# RxPCB_V1-3.net
KiCad netlist of a schematic drawn in EAGLE
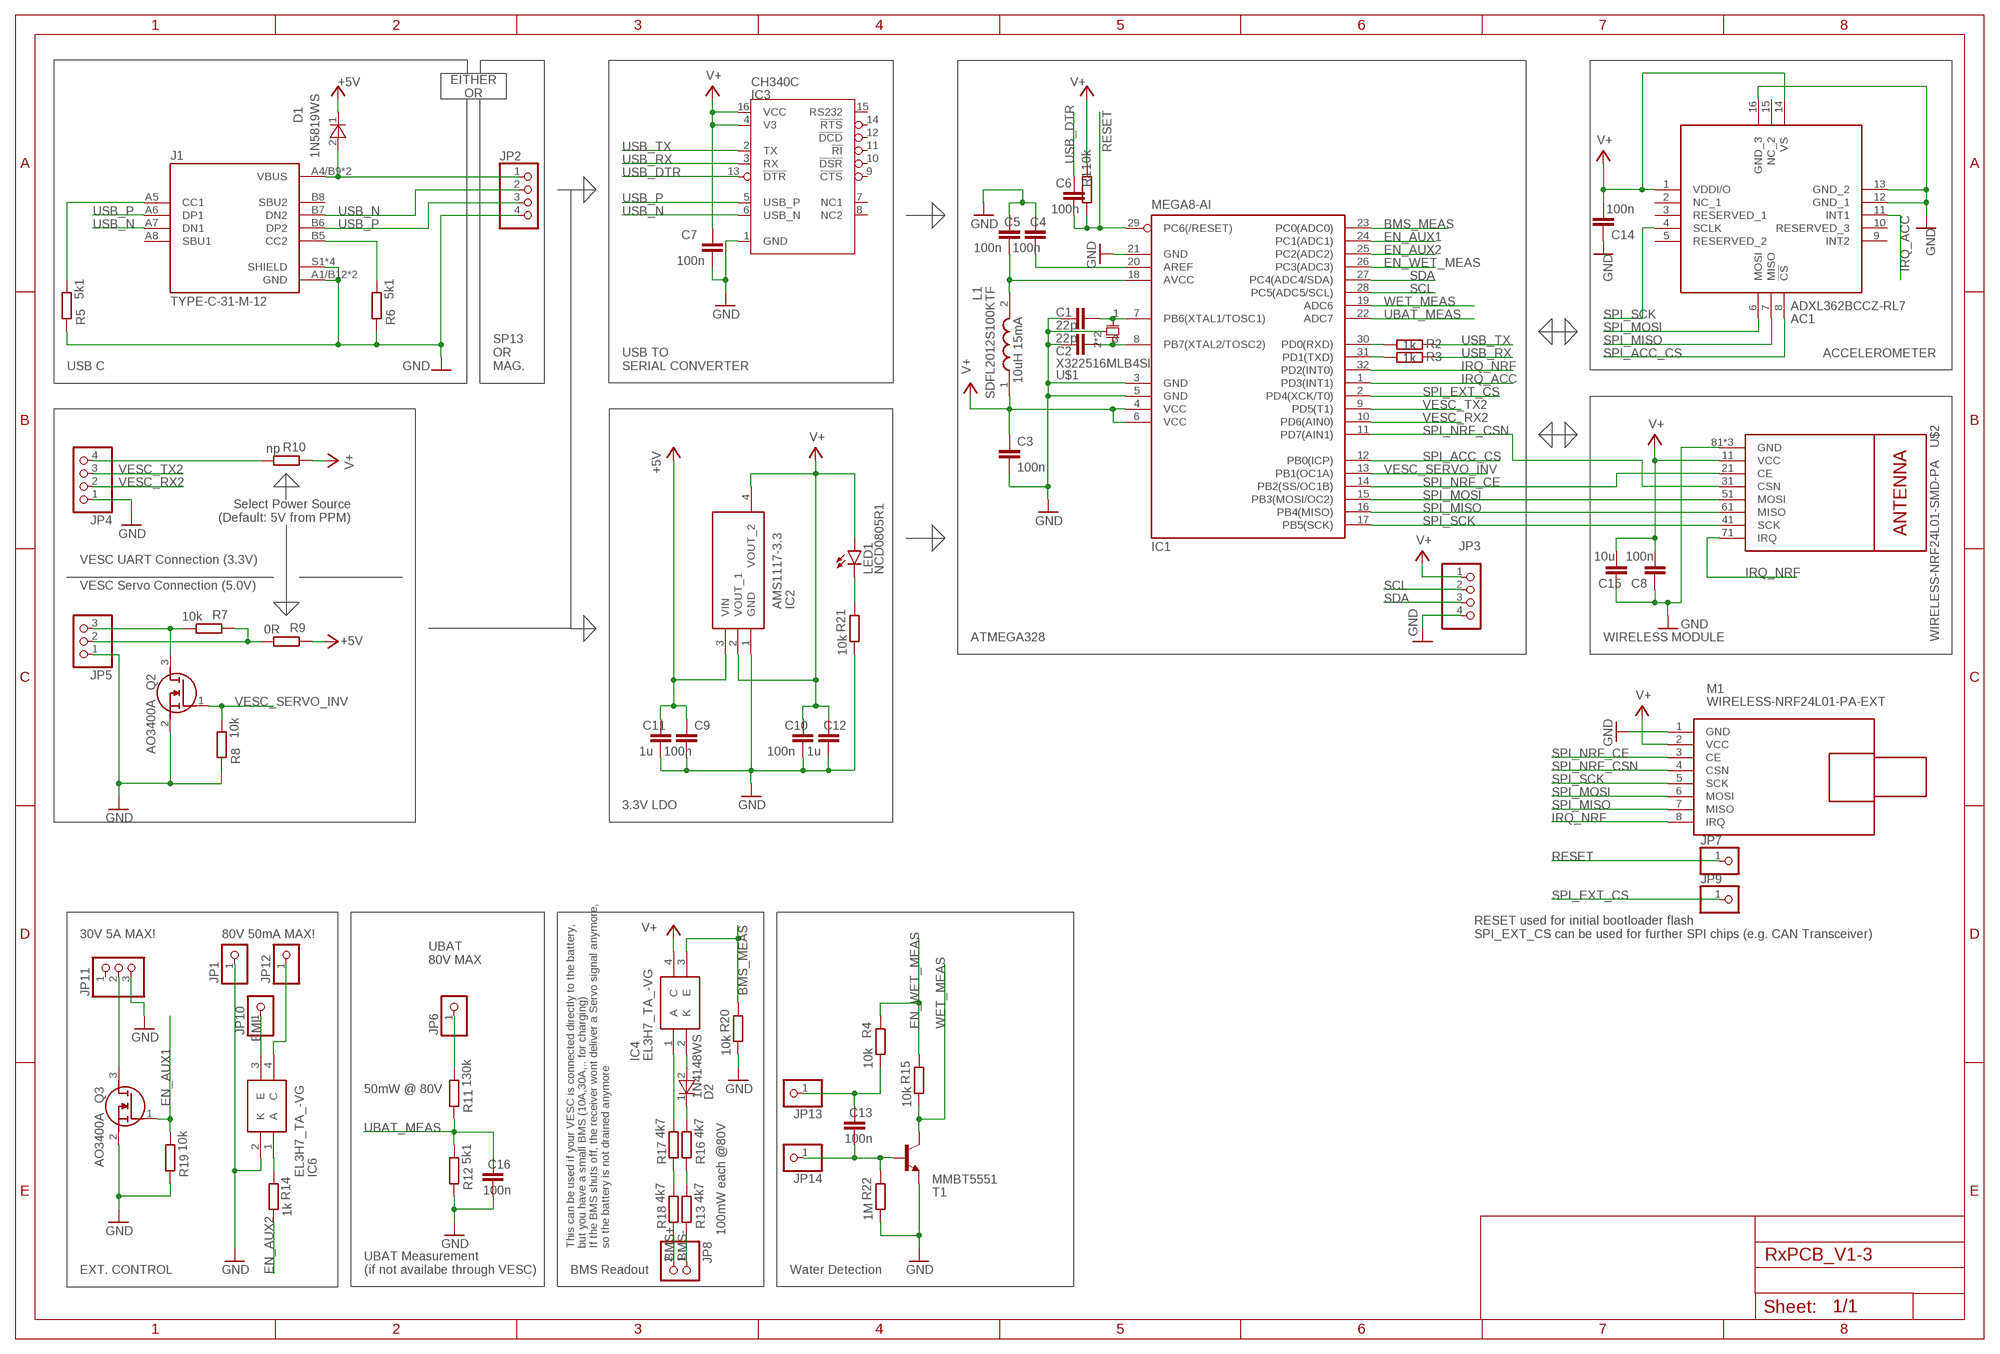
[diagram p0: schematic, sheet 1]

(export (version "E")
  (design (tool "Eeschema 10.0.6"))
  (components
    (comp (ref "AC1")
      (value "ADXL362BCCZ-RL7")
      (footprint "eagle-import:CC-16-4")
      (fields (field (name "MOUSER_PART_NUMBER") "584-ADXL362BCCZ-R7"))
      (libsource (lib "eagle-import") (part "ADXL362BCCZ-RL7"))
    )
    (comp (ref "C1")
      (value "22p")
      (footprint "eagle-import:C0603")
      (libsource (lib "eagle-import") (part "C-EUC0603"))
    )
    (comp (ref "C2")
      (value "22p")
      (footprint "eagle-import:C0603")
      (libsource (lib "eagle-import") (part "C-EUC0603"))
    )
    (comp (ref "C3")
      (value "100n")
      (footprint "eagle-import:C0603")
      (libsource (lib "eagle-import") (part "C-EUC0603"))
    )
    (comp (ref "C4")
      (value "100n")
      (footprint "eagle-import:C0603")
      (libsource (lib "eagle-import") (part "C-EUC0603"))
    )
    (comp (ref "C5")
      (value "100n")
      (footprint "eagle-import:C0603")
      (libsource (lib "eagle-import") (part "C-EUC0603"))
    )
    (comp (ref "C6")
      (value "100n")
      (footprint "eagle-import:C0603")
      (libsource (lib "eagle-import") (part "C-EUC0603"))
    )
    (comp (ref "C7")
      (value "100n")
      (footprint "eagle-import:C0603")
      (libsource (lib "eagle-import") (part "C-EUC0603"))
    )
    (comp (ref "C8")
      (value "100n")
      (footprint "eagle-import:C0603")
      (libsource (lib "eagle-import") (part "C-EUC0603"))
    )
    (comp (ref "C9")
      (value "100n")
      (footprint "eagle-import:C0603")
      (libsource (lib "eagle-import") (part "C-EUC0603"))
    )
    (comp (ref "C10")
      (value "100n")
      (footprint "eagle-import:C0603")
      (libsource (lib "eagle-import") (part "C-EUC0603"))
    )
    (comp (ref "C11")
      (value "1u")
      (footprint "eagle-import:C0603")
      (libsource (lib "eagle-import") (part "C-EUC0603"))
    )
    (comp (ref "C12")
      (value "1u")
      (footprint "eagle-import:C0603")
      (libsource (lib "eagle-import") (part "C-EUC0603"))
    )
    (comp (ref "C13")
      (value "100n")
      (footprint "eagle-import:C0603")
      (libsource (lib "eagle-import") (part "C-EUC0603"))
    )
    (comp (ref "C14")
      (value "100n")
      (footprint "eagle-import:C0603")
      (libsource (lib "eagle-import") (part "C-EUC0603"))
    )
    (comp (ref "C15")
      (value "10u")
      (footprint "eagle-import:C0603")
      (libsource (lib "eagle-import") (part "C-EUC0603"))
    )
    (comp (ref "C16")
      (value "100n")
      (footprint "eagle-import:C0603")
      (libsource (lib "eagle-import") (part "C-EUC0603"))
    )
    (comp (ref "D1")
      (value "1N5819WS")
      (footprint "eagle-import:SODFL2512X90N")
      (fields
        (field (name "ARROW_PART_NUMBER") "1N4148WS")
        (field (name "MOUSER_PART_NUMBER") "512-1N4148WS")
      )
      (libsource (lib "eagle-import") (part "1N4148WS"))
    )
    (comp (ref "D2")
      (value "1N4148WS")
      (footprint "eagle-import:SODFL2512X90N")
      (fields (field (name "MOUSER_PART_NUMBER") "512-1N4148WS"))
      (libsource (lib "eagle-import") (part "1N4148WS"))
    )
    (comp (ref "IC1")
      (value "MEGA8-AI")
      (footprint "eagle-import:TQFP32-08")
      (fields (field (name "MPN") "ATMEGA8-16AU"))
      (libsource (lib "eagle-import") (part "MEGA8-AI"))
    )
    (comp (ref "IC2")
      (value "AMS1117-3.3")
      (footprint "eagle-import:SOT229P700X180-4N")
      (libsource (lib "eagle-import") (part "AMS1117-3.3"))
    )
    (comp (ref "IC3")
      (value "CH340C")
      (footprint "eagle-import:SOIC16N")
      (libsource (lib "eagle-import") (part "CH340G"))
    )
    (comp (ref "IC4")
      (value "EL3H7_TA_-VG")
      (footprint "eagle-import:SOIC127P700X200-4N")
      (fields
        (field (name "ARROW_PART_NUMBER") "EL3H7(TA)-VG")
        (field (name "MOUSER_PART_NUMBER") "638-EL3H7TAVG")
      )
      (libsource (lib "eagle-import") (part "EL3H7_TA_-VG"))
    )
    (comp (ref "IC6")
      (value "EL3H7_TA_-VG")
      (footprint "eagle-import:SOIC127P700X200-4N")
      (fields
        (field (name "ARROW_PART_NUMBER") "EL3H7(TA)-VG")
        (field (name "MOUSER_PART_NUMBER") "638-EL3H7TAVG")
      )
      (libsource (lib "eagle-import") (part "EL3H7_TA_-VG"))
    )
    (comp (ref "J1")
      (value "TYPE-C-31-M-12")
      (footprint "eagle-import:HRO_TYPE-C-31-M-12")
      (fields (field (name "MF") "HRO Electronics Co., Ltd."))
      (libsource (lib "eagle-import") (part "TYPE-C-31-M-12"))
    )
    (comp (ref "JP1")
      (value "PINHD-1X1")
      (footprint "eagle-import:1X01")
      (libsource (lib "eagle-import") (part "PINHD-1X1"))
    )
    (comp (ref "JP2")
      (value "PINHD-1X4")
      (footprint "eagle-import:1X04")
      (libsource (lib "eagle-import") (part "PINHD-1X4"))
    )
    (comp (ref "JP3")
      (value "PINHD-1X4")
      (footprint "eagle-import:1X04")
      (libsource (lib "eagle-import") (part "PINHD-1X4"))
    )
    (comp (ref "JP4")
      (value "PINHD-1X4")
      (footprint "eagle-import:1X04")
      (libsource (lib "eagle-import") (part "PINHD-1X4"))
    )
    (comp (ref "JP5")
      (value "PINHD-1X3")
      (footprint "eagle-import:1X03")
      (libsource (lib "eagle-import") (part "PINHD-1X3"))
    )
    (comp (ref "JP6")
      (value "PINHD-1X1")
      (footprint "eagle-import:1X01")
      (libsource (lib "eagle-import") (part "PINHD-1X1"))
    )
    (comp (ref "JP7")
      (value "PINHD-1X1")
      (footprint "eagle-import:1X01")
      (libsource (lib "eagle-import") (part "PINHD-1X1"))
    )
    (comp (ref "JP8")
      (value "PINHD-1X2")
      (footprint "eagle-import:1X02")
      (libsource (lib "eagle-import") (part "PINHD-1X2"))
    )
    (comp (ref "JP9")
      (value "PINHD-1X1")
      (footprint "eagle-import:1X01")
      (libsource (lib "eagle-import") (part "PINHD-1X1"))
    )
    (comp (ref "JP10")
      (value "PINHD-1X1")
      (footprint "eagle-import:1X01")
      (libsource (lib "eagle-import") (part "PINHD-1X1"))
    )
    (comp (ref "JP11")
      (value "PINHD-1X3")
      (footprint "eagle-import:1X03")
      (libsource (lib "eagle-import") (part "PINHD-1X3"))
    )
    (comp (ref "JP12")
      (value "PINHD-1X1")
      (footprint "eagle-import:1X01")
      (libsource (lib "eagle-import") (part "PINHD-1X1"))
    )
    (comp (ref "JP13")
      (value "PINHD-1X1")
      (footprint "eagle-import:1X01")
      (libsource (lib "eagle-import") (part "PINHD-1X1"))
    )
    (comp (ref "JP14")
      (value "PINHD-1X1")
      (footprint "eagle-import:1X01")
      (libsource (lib "eagle-import") (part "PINHD-1X1"))
    )
    (comp (ref "L1")
      (value "SDFL2012S100KTF")
      (footprint "eagle-import:INDC2112X105N")
      (fields (field (name "MANUFACTURER_PART_NUMBER") "SDFL2012Q2R7KTF"))
      (libsource (lib "eagle-import") (part "SDFL2012Q2R7KTF"))
    )
    (comp (ref "LED1")
      (value "NCD0805R1")
      (footprint "eagle-import:CHIP-LED0805")
      (libsource (lib "eagle-import") (part "LEDCHIP-LED0805"))
    )
    (comp (ref "M1")
      (value "WIRELESS-NRF24L01-PA-EXT")
      (footprint "eagle-import:WIRELESS-NRF24L01-PA-EXT")
      (libsource (lib "eagle-import") (part "WIRELESS-NRF24L01-PA-EXT"))
    )
    (comp (ref "Q2")
      (value "AO3400A")
      (footprint "eagle-import:SOT95P280X125-3N")
      (libsource (lib "eagle-import") (part "AO3400A"))
    )
    (comp (ref "Q3")
      (value "AO3400A")
      (footprint "eagle-import:SOT95P280X125-3N")
      (libsource (lib "eagle-import") (part "AO3400A"))
    )
    (comp (ref "R1")
      (value "10k")
      (footprint "eagle-import:R0603")
      (libsource (lib "eagle-import") (part "R-EU_R0603"))
    )
    (comp (ref "R2")
      (value "1k")
      (footprint "eagle-import:R0603")
      (libsource (lib "eagle-import") (part "R-EU_R0603"))
    )
    (comp (ref "R3")
      (value "1k")
      (footprint "eagle-import:R0603")
      (libsource (lib "eagle-import") (part "R-EU_R0603"))
    )
    (comp (ref "R4")
      (value "10k")
      (footprint "eagle-import:R0603")
      (libsource (lib "eagle-import") (part "R-EU_R0603"))
    )
    (comp (ref "R5")
      (value "5k1")
      (footprint "eagle-import:R0603")
      (libsource (lib "eagle-import") (part "R-EU_R0603"))
    )
    (comp (ref "R6")
      (value "5k1")
      (footprint "eagle-import:R0603")
      (libsource (lib "eagle-import") (part "R-EU_R0603"))
    )
    (comp (ref "R7")
      (value "10k")
      (footprint "eagle-import:R0603")
      (libsource (lib "eagle-import") (part "R-EU_R0603"))
    )
    (comp (ref "R8")
      (value "10k")
      (footprint "eagle-import:R0603")
      (libsource (lib "eagle-import") (part "R-EU_R0603"))
    )
    (comp (ref "R9")
      (value "0R")
      (footprint "eagle-import:R0603")
      (libsource (lib "eagle-import") (part "R-EU_R0603"))
    )
    (comp (ref "R10")
      (value "np")
      (footprint "eagle-import:R0603")
      (libsource (lib "eagle-import") (part "R-EU_R0603"))
    )
    (comp (ref "R11")
      (value "130k")
      (footprint "eagle-import:R0603")
      (libsource (lib "eagle-import") (part "R-EU_R0603"))
    )
    (comp (ref "R12")
      (value "5k1")
      (footprint "eagle-import:R0603")
      (libsource (lib "eagle-import") (part "R-EU_R0603"))
    )
    (comp (ref "R13")
      (value "4k7")
      (footprint "eagle-import:R0603")
      (libsource (lib "eagle-import") (part "R-EU_R0603"))
    )
    (comp (ref "R14")
      (value "1k")
      (footprint "eagle-import:R0603")
      (libsource (lib "eagle-import") (part "R-EU_R0603"))
    )
    (comp (ref "R15")
      (value "10k")
      (footprint "eagle-import:R0603")
      (libsource (lib "eagle-import") (part "R-EU_R0603"))
    )
    (comp (ref "R16")
      (value "4k7")
      (footprint "eagle-import:R0603")
      (libsource (lib "eagle-import") (part "R-EU_R0603"))
    )
    (comp (ref "R17")
      (value "4k7")
      (footprint "eagle-import:R0603")
      (libsource (lib "eagle-import") (part "R-EU_R0603"))
    )
    (comp (ref "R18")
      (value "4k7")
      (footprint "eagle-import:R0603")
      (libsource (lib "eagle-import") (part "R-EU_R0603"))
    )
    (comp (ref "R19")
      (value "10k")
      (footprint "eagle-import:R0603")
      (libsource (lib "eagle-import") (part "R-EU_R0603"))
    )
    (comp (ref "R20")
      (value "10k")
      (footprint "eagle-import:R0603")
      (libsource (lib "eagle-import") (part "R-EU_R0603"))
    )
    (comp (ref "R21")
      (value "10k")
      (footprint "eagle-import:R0603")
      (libsource (lib "eagle-import") (part "R-EU_R0603"))
    )
    (comp (ref "R22")
      (value "1M")
      (footprint "eagle-import:R0603")
      (libsource (lib "eagle-import") (part "R-EU_R0603"))
    )
    (comp (ref "T1")
      (value "MMBT5551")
      (footprint "eagle-import:SOT23-BEC")
      (libsource (lib "eagle-import") (part "-NPN-SOT23-BECBC847B"))
    )
    (comp (ref "U$1")
      (value "X322516MLB4SI")
      (footprint "eagle-import:X322516MLB4SI")
      (libsource (lib "eagle-import") (part "X322516_BETTER"))
    )
    (comp (ref "U$2")
      (value "WIRELESS-NRF24L01-SMD-PA")
      (footprint "eagle-import:WIRELESS-NRF24L01_SMD_PA")
      (libsource (lib "eagle-import") (part "WIRELESS-NRF24L01-SMD-PA"))
    )
  )
  (nets
    (net (code "1") (name "+5V") (class "Default")
      (node (ref "C11") (pin "1") (pinfunction "1_1") (pintype "passive"))
      (node (ref "C9") (pin "1") (pinfunction "1_1") (pintype "passive"))
      (node (ref "D1") (pin "1") (pinfunction "K_1") (pintype "bidirectional"))
      (node (ref "IC2") (pin "3") (pinfunction "VIN_3") (pintype "bidirectional"))
      (node (ref "R9") (pin "1") (pinfunction "1_1") (pintype "passive"))
    )
    (net (code "2") (name "/BMS+") (class "Default")
      (node (ref "JP8") (pin "2") (pinfunction "2_2") (pintype "passive"))
      (node (ref "R18") (pin "1") (pinfunction "1_1") (pintype "passive"))
    )
    (net (code "3") (name "/BMS-") (class "Default")
      (node (ref "JP8") (pin "1") (pinfunction "1_1") (pintype "passive"))
      (node (ref "R13") (pin "1") (pinfunction "1_1") (pintype "passive"))
    )
    (net (code "4") (name "/BMS_MEAS") (class "Default")
      (node (ref "IC1") (pin "23") (pinfunction "PC0(ADC0)_23") (pintype "bidirectional"))
      (node (ref "IC4") (pin "3") (pinfunction "E_3") (pintype "bidirectional"))
      (node (ref "R20") (pin "1") (pinfunction "1_1") (pintype "passive"))
    )
    (net (code "5") (name "/EMI") (class "Default")
      (node (ref "IC6") (pin "3") (pinfunction "E_3") (pintype "bidirectional"))
      (node (ref "JP10") (pin "1") (pinfunction "1_1") (pintype "passive"))
    )
    (net (code "6") (name "/EN_AUX1") (class "Default")
      (node (ref "IC1") (pin "24") (pinfunction "PC1(ADC1)_24") (pintype "bidirectional"))
      (node (ref "Q3") (pin "1") (pinfunction "G_1") (pintype "bidirectional"))
      (node (ref "R19") (pin "2") (pinfunction "2_2") (pintype "passive"))
    )
    (net (code "7") (name "/EN_AUX2") (class "Default")
      (node (ref "IC1") (pin "25") (pinfunction "PC2(ADC2)_25") (pintype "bidirectional"))
      (node (ref "R14") (pin "2") (pinfunction "2_2") (pintype "passive"))
    )
    (net (code "8") (name "/EN_WET_MEAS") (class "Default")
      (node (ref "IC1") (pin "26") (pinfunction "PC3(ADC3)_26") (pintype "bidirectional"))
      (node (ref "R15") (pin "1") (pinfunction "1_1") (pintype "passive"))
      (node (ref "R4") (pin "1") (pinfunction "1_1") (pintype "passive"))
    )
    (net (code "9") (name "/IRQ_ACC") (class "Default")
      (node (ref "AC1") (pin "11") (pinfunction "INT1_11") (pintype "input"))
      (node (ref "IC1") (pin "1") (pinfunction "PD3(INT1)_1") (pintype "bidirectional"))
    )
    (net (code "10") (name "/IRQ_NRF") (class "Default")
      (node (ref "IC1") (pin "32") (pinfunction "PD2(INT0)_32") (pintype "bidirectional"))
      (node (ref "M1") (pin "8") (pinfunction "IRQ_8") (pintype "bidirectional"))
      (node (ref "U$2") (pin "71") (pinfunction "IRQ_71") (pintype "bidirectional"))
    )
    (net (code "11") (name "/RESET") (class "Default")
      (node (ref "C6") (pin "2") (pinfunction "2_2") (pintype "passive"))
      (node (ref "IC1") (pin "29") (pinfunction "PC6(/RESET)_29") (pintype "bidirectional"))
      (node (ref "JP7") (pin "1") (pinfunction "1_1") (pintype "passive"))
      (node (ref "R1") (pin "1") (pinfunction "1_1") (pintype "passive"))
    )
    (net (code "12") (name "/SCL") (class "Default")
      (node (ref "IC1") (pin "28") (pinfunction "PC5(ADC5/SCL)_28") (pintype "bidirectional"))
      (node (ref "JP3") (pin "2") (pinfunction "2_2") (pintype "passive"))
    )
    (net (code "13") (name "/SDA") (class "Default")
      (node (ref "IC1") (pin "27") (pinfunction "PC4(ADC4/SDA)_27") (pintype "bidirectional"))
      (node (ref "JP3") (pin "3") (pinfunction "3_3") (pintype "passive"))
    )
    (net (code "14") (name "/SPI_ACC_CS") (class "Default")
      (node (ref "AC1") (pin "8") (pinfunction "~{CS}_8") (pintype "input"))
      (node (ref "IC1") (pin "12") (pinfunction "PB0(ICP)_12") (pintype "bidirectional"))
    )
    (net (code "15") (name "/SPI_EXT_CS") (class "Default")
      (node (ref "IC1") (pin "2") (pinfunction "PD4(XCK/T0)_2") (pintype "bidirectional"))
      (node (ref "JP9") (pin "1") (pinfunction "1_1") (pintype "passive"))
    )
    (net (code "16") (name "/SPI_MISO") (class "Default")
      (node (ref "AC1") (pin "7") (pinfunction "MISO_7") (pintype "bidirectional"))
      (node (ref "IC1") (pin "16") (pinfunction "PB4(MISO)_16") (pintype "bidirectional"))
      (node (ref "M1") (pin "7") (pinfunction "MISO_7") (pintype "bidirectional"))
      (node (ref "U$2") (pin "61") (pinfunction "MISO_61") (pintype "bidirectional"))
    )
    (net (code "17") (name "/SPI_MOSI") (class "Default")
      (node (ref "AC1") (pin "6") (pinfunction "MOSI_6") (pintype "bidirectional"))
      (node (ref "IC1") (pin "15") (pinfunction "PB3(MOSI/OC2)_15") (pintype "bidirectional"))
      (node (ref "M1") (pin "6") (pinfunction "MOSI_6") (pintype "bidirectional"))
      (node (ref "U$2") (pin "51") (pinfunction "MOSI_51") (pintype "bidirectional"))
    )
    (net (code "18") (name "/SPI_NRF_CE") (class "Default")
      (node (ref "IC1") (pin "14") (pinfunction "PB2(SS/OC1B)_14") (pintype "bidirectional"))
      (node (ref "M1") (pin "3") (pinfunction "CE_3") (pintype "bidirectional"))
      (node (ref "U$2") (pin "21") (pinfunction "CE_21") (pintype "bidirectional"))
    )
    (net (code "19") (name "/SPI_NRF_CSN") (class "Default")
      (node (ref "IC1") (pin "11") (pinfunction "PD7(AIN1)_11") (pintype "bidirectional"))
      (node (ref "M1") (pin "4") (pinfunction "CSN_4") (pintype "bidirectional"))
      (node (ref "U$2") (pin "31") (pinfunction "CSN_31") (pintype "bidirectional"))
    )
    (net (code "20") (name "/SPI_SCK") (class "Default")
      (node (ref "AC1") (pin "4") (pinfunction "SCLK_4") (pintype "input"))
      (node (ref "IC1") (pin "17") (pinfunction "PB5(SCK)_17") (pintype "bidirectional"))
      (node (ref "M1") (pin "5") (pinfunction "SCK_5") (pintype "bidirectional"))
      (node (ref "U$2") (pin "41") (pinfunction "SCK_41") (pintype "bidirectional"))
    )
    (net (code "21") (name "/UBAT_MEAS") (class "Default")
      (node (ref "C16") (pin "1") (pinfunction "1_1") (pintype "passive"))
      (node (ref "IC1") (pin "22") (pinfunction "ADC7_22") (pintype "bidirectional"))
      (node (ref "R11") (pin "1") (pinfunction "1_1") (pintype "passive"))
      (node (ref "R12") (pin "2") (pinfunction "2_2") (pintype "passive"))
    )
    (net (code "22") (name "/USB_DTR") (class "Default")
      (node (ref "C6") (pin "1") (pinfunction "1_1") (pintype "passive"))
      (node (ref "IC3") (pin "13") (pinfunction "~{DTR}_13") (pintype "output"))
    )
    (net (code "23") (name "/USB_N") (class "Default")
      (node (ref "IC3") (pin "6") (pinfunction "USB_N_6") (pintype "bidirectional"))
      (node (ref "J1") (pin "A7") (pinfunction "DN1_A7") (pintype "bidirectional"))
      (node (ref "J1") (pin "B7") (pinfunction "DN2_B7") (pintype "bidirectional"))
      (node (ref "JP2") (pin "2") (pinfunction "2_2") (pintype "passive"))
    )
    (net (code "24") (name "/USB_P") (class "Default")
      (node (ref "IC3") (pin "5") (pinfunction "USB_P_5") (pintype "bidirectional"))
      (node (ref "J1") (pin "A6") (pinfunction "DP1_A6") (pintype "bidirectional"))
      (node (ref "J1") (pin "B6") (pinfunction "DP2_B6") (pintype "bidirectional"))
      (node (ref "JP2") (pin "3") (pinfunction "3_3") (pintype "passive"))
    )
    (net (code "25") (name "/USB_RX") (class "Default")
      (node (ref "IC3") (pin "3") (pinfunction "RX_3") (pintype "input"))
      (node (ref "R3") (pin "1") (pinfunction "1_1") (pintype "passive"))
    )
    (net (code "26") (name "/USB_TX") (class "Default")
      (node (ref "IC3") (pin "2") (pinfunction "TX_2") (pintype "output"))
      (node (ref "R2") (pin "1") (pinfunction "1_1") (pintype "passive"))
    )
    (net (code "27") (name "/VESC_RX2") (class "Default")
      (node (ref "IC1") (pin "10") (pinfunction "PD6(AIN0)_10") (pintype "bidirectional"))
      (node (ref "JP4") (pin "2") (pinfunction "2_2") (pintype "passive"))
    )
    (net (code "28") (name "/VESC_SERVO_INV") (class "Default")
      (node (ref "IC1") (pin "13") (pinfunction "PB1(OC1A)_13") (pintype "bidirectional"))
      (node (ref "Q2") (pin "1") (pinfunction "G_1") (pintype "bidirectional"))
      (node (ref "R8") (pin "2") (pinfunction "2_2") (pintype "passive"))
    )
    (net (code "29") (name "/VESC_TX2") (class "Default")
      (node (ref "IC1") (pin "9") (pinfunction "PD5(T1)_9") (pintype "bidirectional"))
      (node (ref "JP4") (pin "3") (pinfunction "3_3") (pintype "passive"))
    )
    (net (code "30") (name "/WET_MEAS") (class "Default")
      (node (ref "IC1") (pin "19") (pinfunction "ADC6_19") (pintype "bidirectional"))
      (node (ref "R15") (pin "2") (pinfunction "2_2") (pintype "passive"))
      (node (ref "T1") (pin "C") (pinfunction "C_C") (pintype "passive"))
    )
    (net (code "31") (name "GND") (class "Default")
      (node (ref "AC1") (pin "12") (pinfunction "GND_1_12") (pintype "power_in"))
      (node (ref "AC1") (pin "13") (pinfunction "GND_2_13") (pintype "power_in"))
      (node (ref "AC1") (pin "16") (pinfunction "GND_3_16") (pintype "power_in"))
      (node (ref "C1") (pin "2") (pinfunction "2_2") (pintype "passive"))
      (node (ref "C10") (pin "2") (pinfunction "2_2") (pintype "passive"))
      (node (ref "C11") (pin "2") (pinfunction "2_2") (pintype "passive"))
      (node (ref "C12") (pin "2") (pinfunction "2_2") (pintype "passive"))
      (node (ref "C14") (pin "1") (pinfunction "1_1") (pintype "passive"))
      (node (ref "C15") (pin "2") (pinfunction "2_2") (pintype "passive"))
      (node (ref "C16") (pin "2") (pinfunction "2_2") (pintype "passive"))
      (node (ref "C2") (pin "2") (pinfunction "2_2") (pintype "passive"))
      (node (ref "C3") (pin "2") (pinfunction "2_2") (pintype "passive"))
      (node (ref "C4") (pin "1") (pinfunction "1_1") (pintype "passive"))
      (node (ref "C5") (pin "1") (pinfunction "1_1") (pintype "passive"))
      (node (ref "C7") (pin "2") (pinfunction "2_2") (pintype "passive"))
      (node (ref "C8") (pin "1") (pinfunction "1_1") (pintype "passive"))
      (node (ref "C9") (pin "2") (pinfunction "2_2") (pintype "passive"))
      (node (ref "IC1") (pin "21") (pinfunction "GND_21") (pintype "power_in"))
      (node (ref "IC1") (pin "3") (pinfunction "GND_3") (pintype "power_in"))
      (node (ref "IC1") (pin "5") (pinfunction "GND_5") (pintype "power_in"))
      (node (ref "IC2") (pin "1") (pinfunction "GND_1") (pintype "bidirectional"))
      (node (ref "IC3") (pin "1") (pinfunction "GND_1") (pintype "input"))
      (node (ref "IC6") (pin "2") (pinfunction "K_2") (pintype "bidirectional"))
      (node (ref "J1") (pin "A1/B12") (pinfunction "GND_A1/B12") (pintype "power_in"))
      (node (ref "J1") (pin "B1/A12") (pinfunction "GND_B1/A12") (pintype "power_in"))
      (node (ref "J1") (pin "S1") (pinfunction "SHIELD_S1") (pintype "passive"))
      (node (ref "J1") (pin "S2") (pinfunction "SHIELD_S2") (pintype "passive"))
      (node (ref "J1") (pin "S3") (pinfunction "SHIELD_S3") (pintype "passive"))
      (node (ref "J1") (pin "S4") (pinfunction "SHIELD_S4") (pintype "passive"))
      (node (ref "JP1") (pin "1") (pinfunction "1_1") (pintype "passive"))
      (node (ref "JP11") (pin "3") (pinfunction "3_3") (pintype "passive"))
      (node (ref "JP2") (pin "4") (pinfunction "4_4") (pintype "passive"))
      (node (ref "JP3") (pin "4") (pinfunction "4_4") (pintype "passive"))
      (node (ref "JP4") (pin "1") (pinfunction "1_1") (pintype "passive"))
      (node (ref "JP5") (pin "1") (pinfunction "1_1") (pintype "passive"))
      (node (ref "M1") (pin "1") (pinfunction "GND_1") (pintype "power_in"))
      (node (ref "Q2") (pin "2") (pinfunction "S_2") (pintype "bidirectional"))
      (node (ref "Q3") (pin "2") (pinfunction "S_2") (pintype "bidirectional"))
      (node (ref "R12") (pin "1") (pinfunction "1_1") (pintype "passive"))
      (node (ref "R19") (pin "1") (pinfunction "1_1") (pintype "passive"))
      (node (ref "R20") (pin "2") (pinfunction "2_2") (pintype "passive"))
      (node (ref "R21") (pin "2") (pinfunction "2_2") (pintype "passive"))
      (node (ref "R22") (pin "2") (pinfunction "2_2") (pintype "passive"))
      (node (ref "R5") (pin "1") (pinfunction "1_1") (pintype "passive"))
      (node (ref "R6") (pin "1") (pinfunction "1_1") (pintype "passive"))
      (node (ref "R8") (pin "1") (pinfunction "1_1") (pintype "passive"))
      (node (ref "T1") (pin "E") (pinfunction "E_E") (pintype "passive"))
      (node (ref "U$1") (pin "2") (pinfunction "G_2") (pintype "bidirectional"))
      (node (ref "U$1") (pin "4") (pinfunction "G_4") (pintype "bidirectional"))
      (node (ref "U$2") (pin "81") (pinfunction "GND_81") (pintype "power_in"))
      (node (ref "U$2") (pin "P1") (pinfunction "GND_P1") (pintype "power_in"))
      (node (ref "U$2") (pin "P2") (pinfunction "GND_P2") (pintype "power_in"))
    )
    (net (code "32") (name "Net-(C13-Pad1)") (class "Default")
      (node (ref "C13") (pin "1") (pinfunction "1_1") (pintype "passive"))
      (node (ref "JP13") (pin "1") (pinfunction "1_1") (pintype "passive"))
      (node (ref "R4") (pin "2") (pinfunction "2_2") (pintype "passive"))
    )
    (net (code "33") (name "Net-(C13-Pad2)") (class "Default")
      (node (ref "C13") (pin "2") (pinfunction "2_2") (pintype "passive"))
      (node (ref "JP14") (pin "1") (pinfunction "1_1") (pintype "passive"))
      (node (ref "R22") (pin "1") (pinfunction "1_1") (pintype "passive"))
      (node (ref "T1") (pin "B") (pinfunction "B_B") (pintype "passive"))
    )
    (net (code "34") (name "Net-(D1-A)") (class "Default")
      (node (ref "D1") (pin "2") (pinfunction "A_2") (pintype "bidirectional"))
      (node (ref "J1") (pin "A4/B9") (pinfunction "VBUS_A4/B9") (pintype "power_in"))
      (node (ref "J1") (pin "B4/A9") (pinfunction "VBUS_B4/A9") (pintype "power_in"))
      (node (ref "JP2") (pin "1") (pinfunction "1_1") (pintype "passive"))
    )
    (net (code "35") (name "Net-(D2-A)") (class "Default")
      (node (ref "D2") (pin "2") (pinfunction "A_2") (pintype "bidirectional"))
      (node (ref "IC4") (pin "2") (pinfunction "K_2") (pintype "bidirectional"))
    )
    (net (code "36") (name "Net-(D2-K)") (class "Default")
      (node (ref "D2") (pin "1") (pinfunction "K_1") (pintype "bidirectional"))
      (node (ref "R16") (pin "2") (pinfunction "2_2") (pintype "passive"))
    )
    (net (code "37") (name "Net-(IC1-AREF)") (class "Default")
      (node (ref "C4") (pin "2") (pinfunction "2_2") (pintype "passive"))
      (node (ref "IC1") (pin "20") (pinfunction "AREF_20") (pintype "passive"))
    )
    (net (code "38") (name "Net-(IC1-AVCC)") (class "Default")
      (node (ref "C5") (pin "2") (pinfunction "2_2") (pintype "passive"))
      (node (ref "IC1") (pin "18") (pinfunction "AVCC_18") (pintype "power_in"))
      (node (ref "L1") (pin "2") (pinfunction "2_2") (pintype "bidirectional"))
    )
    (net (code "39") (name "Net-(IC1-PB6(XTAL1{slash}TOSC1))") (class "Default")
      (node (ref "C1") (pin "1") (pinfunction "1_1") (pintype "passive"))
      (node (ref "IC1") (pin "7") (pinfunction "PB6(XTAL1/TOSC1)_7") (pintype "bidirectional"))
      (node (ref "U$1") (pin "1") (pinfunction "X1_1") (pintype "bidirectional"))
    )
    (net (code "40") (name "Net-(IC1-PB7(XTAL2{slash}TOSC2))") (class "Default")
      (node (ref "C2") (pin "1") (pinfunction "1_1") (pintype "passive"))
      (node (ref "IC1") (pin "8") (pinfunction "PB7(XTAL2/TOSC2)_8") (pintype "bidirectional"))
      (node (ref "U$1") (pin "3") (pinfunction "X2_3") (pintype "bidirectional"))
    )
    (net (code "41") (name "Net-(IC1-PD0(RXD))") (class "Default")
      (node (ref "IC1") (pin "30") (pinfunction "PD0(RXD)_30") (pintype "bidirectional"))
      (node (ref "R2") (pin "2") (pinfunction "2_2") (pintype "passive"))
    )
    (net (code "42") (name "Net-(IC1-PD1(TXD))") (class "Default")
      (node (ref "IC1") (pin "31") (pinfunction "PD1(TXD)_31") (pintype "bidirectional"))
      (node (ref "R3") (pin "2") (pinfunction "2_2") (pintype "passive"))
    )
    (net (code "43") (name "Net-(IC4-A)") (class "Default")
      (node (ref "IC4") (pin "1") (pinfunction "A_1") (pintype "bidirectional"))
      (node (ref "R17") (pin "2") (pinfunction "2_2") (pintype "passive"))
    )
    (net (code "44") (name "Net-(IC6-A)") (class "Default")
      (node (ref "IC6") (pin "1") (pinfunction "A_1") (pintype "bidirectional"))
      (node (ref "R14") (pin "1") (pinfunction "1_1") (pintype "passive"))
    )
    (net (code "45") (name "Net-(IC6-C)") (class "Default")
      (node (ref "IC6") (pin "4") (pinfunction "C_4") (pintype "bidirectional"))
      (node (ref "JP12") (pin "1") (pinfunction "1_1") (pintype "passive"))
    )
    (net (code "46") (name "Net-(J1-CC1)") (class "Default")
      (node (ref "J1") (pin "A5") (pinfunction "CC1_A5") (pintype "bidirectional"))
      (node (ref "R5") (pin "2") (pinfunction "2_2") (pintype "passive"))
    )
    (net (code "47") (name "Net-(J1-CC2)") (class "Default")
      (node (ref "J1") (pin "B5") (pinfunction "CC2_B5") (pintype "bidirectional"))
      (node (ref "R6") (pin "2") (pinfunction "2_2") (pintype "passive"))
    )
    (net (code "48") (name "Net-(JP4-Pad4)") (class "Default")
      (node (ref "JP4") (pin "4") (pinfunction "4_4") (pintype "passive"))
      (node (ref "R10") (pin "2") (pinfunction "2_2") (pintype "passive"))
    )
    (net (code "49") (name "Net-(JP5-Pad2)") (class "Default")
      (node (ref "JP5") (pin "2") (pinfunction "2_2") (pintype "passive"))
      (node (ref "R7") (pin "1") (pinfunction "1_1") (pintype "passive"))
      (node (ref "R9") (pin "2") (pinfunction "2_2") (pintype "passive"))
    )
    (net (code "50") (name "Net-(JP6-Pad1)") (class "Default")
      (node (ref "JP6") (pin "1") (pinfunction "1_1") (pintype "passive"))
      (node (ref "R11") (pin "2") (pinfunction "2_2") (pintype "passive"))
    )
    (net (code "51") (name "Net-(LED1-PadC)") (class "Default")
      (node (ref "LED1") (pin "C") (pinfunction "C_C") (pintype "passive"))
      (node (ref "R21") (pin "1") (pinfunction "1_1") (pintype "passive"))
    )
    (net (code "52") (name "Net-(Q2-D)") (class "Default")
      (node (ref "JP5") (pin "3") (pinfunction "3_3") (pintype "passive"))
      (node (ref "Q2") (pin "3") (pinfunction "D_3") (pintype "bidirectional"))
      (node (ref "R7") (pin "2") (pinfunction "2_2") (pintype "passive"))
    )
    (net (code "53") (name "Net-(Q3-D)") (class "Default")
      (node (ref "JP11") (pin "2") (pinfunction "2_2") (pintype "passive"))
      (node (ref "Q3") (pin "3") (pinfunction "D_3") (pintype "bidirectional"))
    )
    (net (code "54") (name "Net-(R13-Pad2)") (class "Default")
      (node (ref "R13") (pin "2") (pinfunction "2_2") (pintype "passive"))
      (node (ref "R16") (pin "1") (pinfunction "1_1") (pintype "passive"))
    )
    (net (code "55") (name "Net-(R17-Pad1)") (class "Default")
      (node (ref "R17") (pin "1") (pinfunction "1_1") (pintype "passive"))
      (node (ref "R18") (pin "2") (pinfunction "2_2") (pintype "passive"))
    )
    (net (code "56") (name "V+") (class "Default")
      (node (ref "AC1") (pin "1") (pinfunction "VDDI/O_1") (pintype "power_in"))
      (node (ref "AC1") (pin "14") (pinfunction "VS_14") (pintype "bidirectional"))
      (node (ref "C10") (pin "1") (pinfunction "1_1") (pintype "passive"))
      (node (ref "C12") (pin "1") (pinfunction "1_1") (pintype "passive"))
      (node (ref "C14") (pin "2") (pinfunction "2_2") (pintype "passive"))
      (node (ref "C15") (pin "1") (pinfunction "1_1") (pintype "passive"))
      (node (ref "C3") (pin "1") (pinfunction "1_1") (pintype "passive"))
      (node (ref "C7") (pin "1") (pinfunction "1_1") (pintype "passive"))
      (node (ref "C8") (pin "2") (pinfunction "2_2") (pintype "passive"))
      (node (ref "IC1") (pin "4") (pinfunction "VCC_4") (pintype "power_in"))
      (node (ref "IC1") (pin "6") (pinfunction "VCC_6") (pintype "power_in"))
      (node (ref "IC2") (pin "2") (pinfunction "VOUT_1_2") (pintype "bidirectional"))
      (node (ref "IC2") (pin "4") (pinfunction "VOUT_2_4") (pintype "bidirectional"))
      (node (ref "IC3") (pin "16") (pinfunction "VCC_16") (pintype "input"))
      (node (ref "IC3") (pin "4") (pinfunction "V3_4") (pintype "output"))
      (node (ref "IC4") (pin "4") (pinfunction "C_4") (pintype "bidirectional"))
      (node (ref "JP3") (pin "1") (pinfunction "1_1") (pintype "passive"))
      (node (ref "L1") (pin "1") (pinfunction "1_1") (pintype "bidirectional"))
      (node (ref "LED1") (pin "A") (pinfunction "A_A") (pintype "passive"))
      (node (ref "M1") (pin "2") (pinfunction "VCC_2") (pintype "power_in"))
      (node (ref "R1") (pin "2") (pinfunction "2_2") (pintype "passive"))
      (node (ref "R10") (pin "1") (pinfunction "1_1") (pintype "passive"))
      (node (ref "U$2") (pin "11") (pinfunction "VCC_11") (pintype "power_in"))
    )
    (net (code "57") (name "unconnected-(AC1-INT2-Pad9)") (class "Default")
      (node (ref "AC1") (pin "9") (pinfunction "INT2_9") (pintype "input"))
    )
    (net (code "58") (name "unconnected-(AC1-NC_1-Pad2)") (class "Default")
      (node (ref "AC1") (pin "2") (pinfunction "NC_1_2") (pintype "bidirectional"))
    )
    (net (code "59") (name "unconnected-(AC1-NC_2-Pad15)") (class "Default")
      (node (ref "AC1") (pin "15") (pinfunction "NC_2_15") (pintype "bidirectional"))
    )
    (net (code "60") (name "unconnected-(AC1-RESERVED_1-Pad3)") (class "Default")
      (node (ref "AC1") (pin "3") (pinfunction "RESERVED_1_3") (pintype "bidirectional"))
    )
    (net (code "61") (name "unconnected-(AC1-RESERVED_2-Pad5)") (class "Default")
      (node (ref "AC1") (pin "5") (pinfunction "RESERVED_2_5") (pintype "bidirectional"))
    )
    (net (code "62") (name "unconnected-(AC1-RESERVED_3-Pad10)") (class "Default")
      (node (ref "AC1") (pin "10") (pinfunction "RESERVED_3_10") (pintype "bidirectional"))
    )
    (net (code "63") (name "unconnected-(IC3-NC1-Pad7)") (class "Default")
      (node (ref "IC3") (pin "7") (pinfunction "NC1_7") (pintype "no_connect"))
    )
    (net (code "64") (name "unconnected-(IC3-NC2-Pad8)") (class "Default")
      (node (ref "IC3") (pin "8") (pinfunction "NC2_8") (pintype "no_connect"))
    )
    (net (code "65") (name "unconnected-(IC3-RS232-Pad15)") (class "Default")
      (node (ref "IC3") (pin "15") (pinfunction "RS232_15") (pintype "input"))
    )
    (net (code "66") (name "unconnected-(IC3-~{CTS}-Pad9)") (class "Default")
      (node (ref "IC3") (pin "9") (pinfunction "~{CTS}_9") (pintype "input"))
    )
    (net (code "67") (name "unconnected-(IC3-~{DCD}-Pad12)") (class "Default")
      (node (ref "IC3") (pin "12") (pinfunction "~{DCD}_12") (pintype "input"))
    )
    (net (code "68") (name "unconnected-(IC3-~{DSR}-Pad10)") (class "Default")
      (node (ref "IC3") (pin "10") (pinfunction "~{DSR}_10") (pintype "input"))
    )
    (net (code "69") (name "unconnected-(IC3-~{RI}-Pad11)") (class "Default")
      (node (ref "IC3") (pin "11") (pinfunction "~{RI}_11") (pintype "input"))
    )
    (net (code "70") (name "unconnected-(IC3-~{RTS}-Pad14)") (class "Default")
      (node (ref "IC3") (pin "14") (pinfunction "~{RTS}_14") (pintype "output"))
    )
    (net (code "71") (name "unconnected-(J1-SBU1-PadA8)") (class "Default")
      (node (ref "J1") (pin "A8") (pinfunction "SBU1_A8") (pintype "bidirectional"))
    )
    (net (code "72") (name "unconnected-(J1-SBU2-PadB8)") (class "Default")
      (node (ref "J1") (pin "B8") (pinfunction "SBU2_B8") (pintype "bidirectional"))
    )
    (net (code "73") (name "unconnected-(JP11-Pad1)") (class "Default")
      (node (ref "JP11") (pin "1") (pinfunction "1_1") (pintype "passive"))
    )
  )
)
